# 12-USB_Phy_and_Hub.net
KiCad netlist of a schematic drawn in Altium Designer
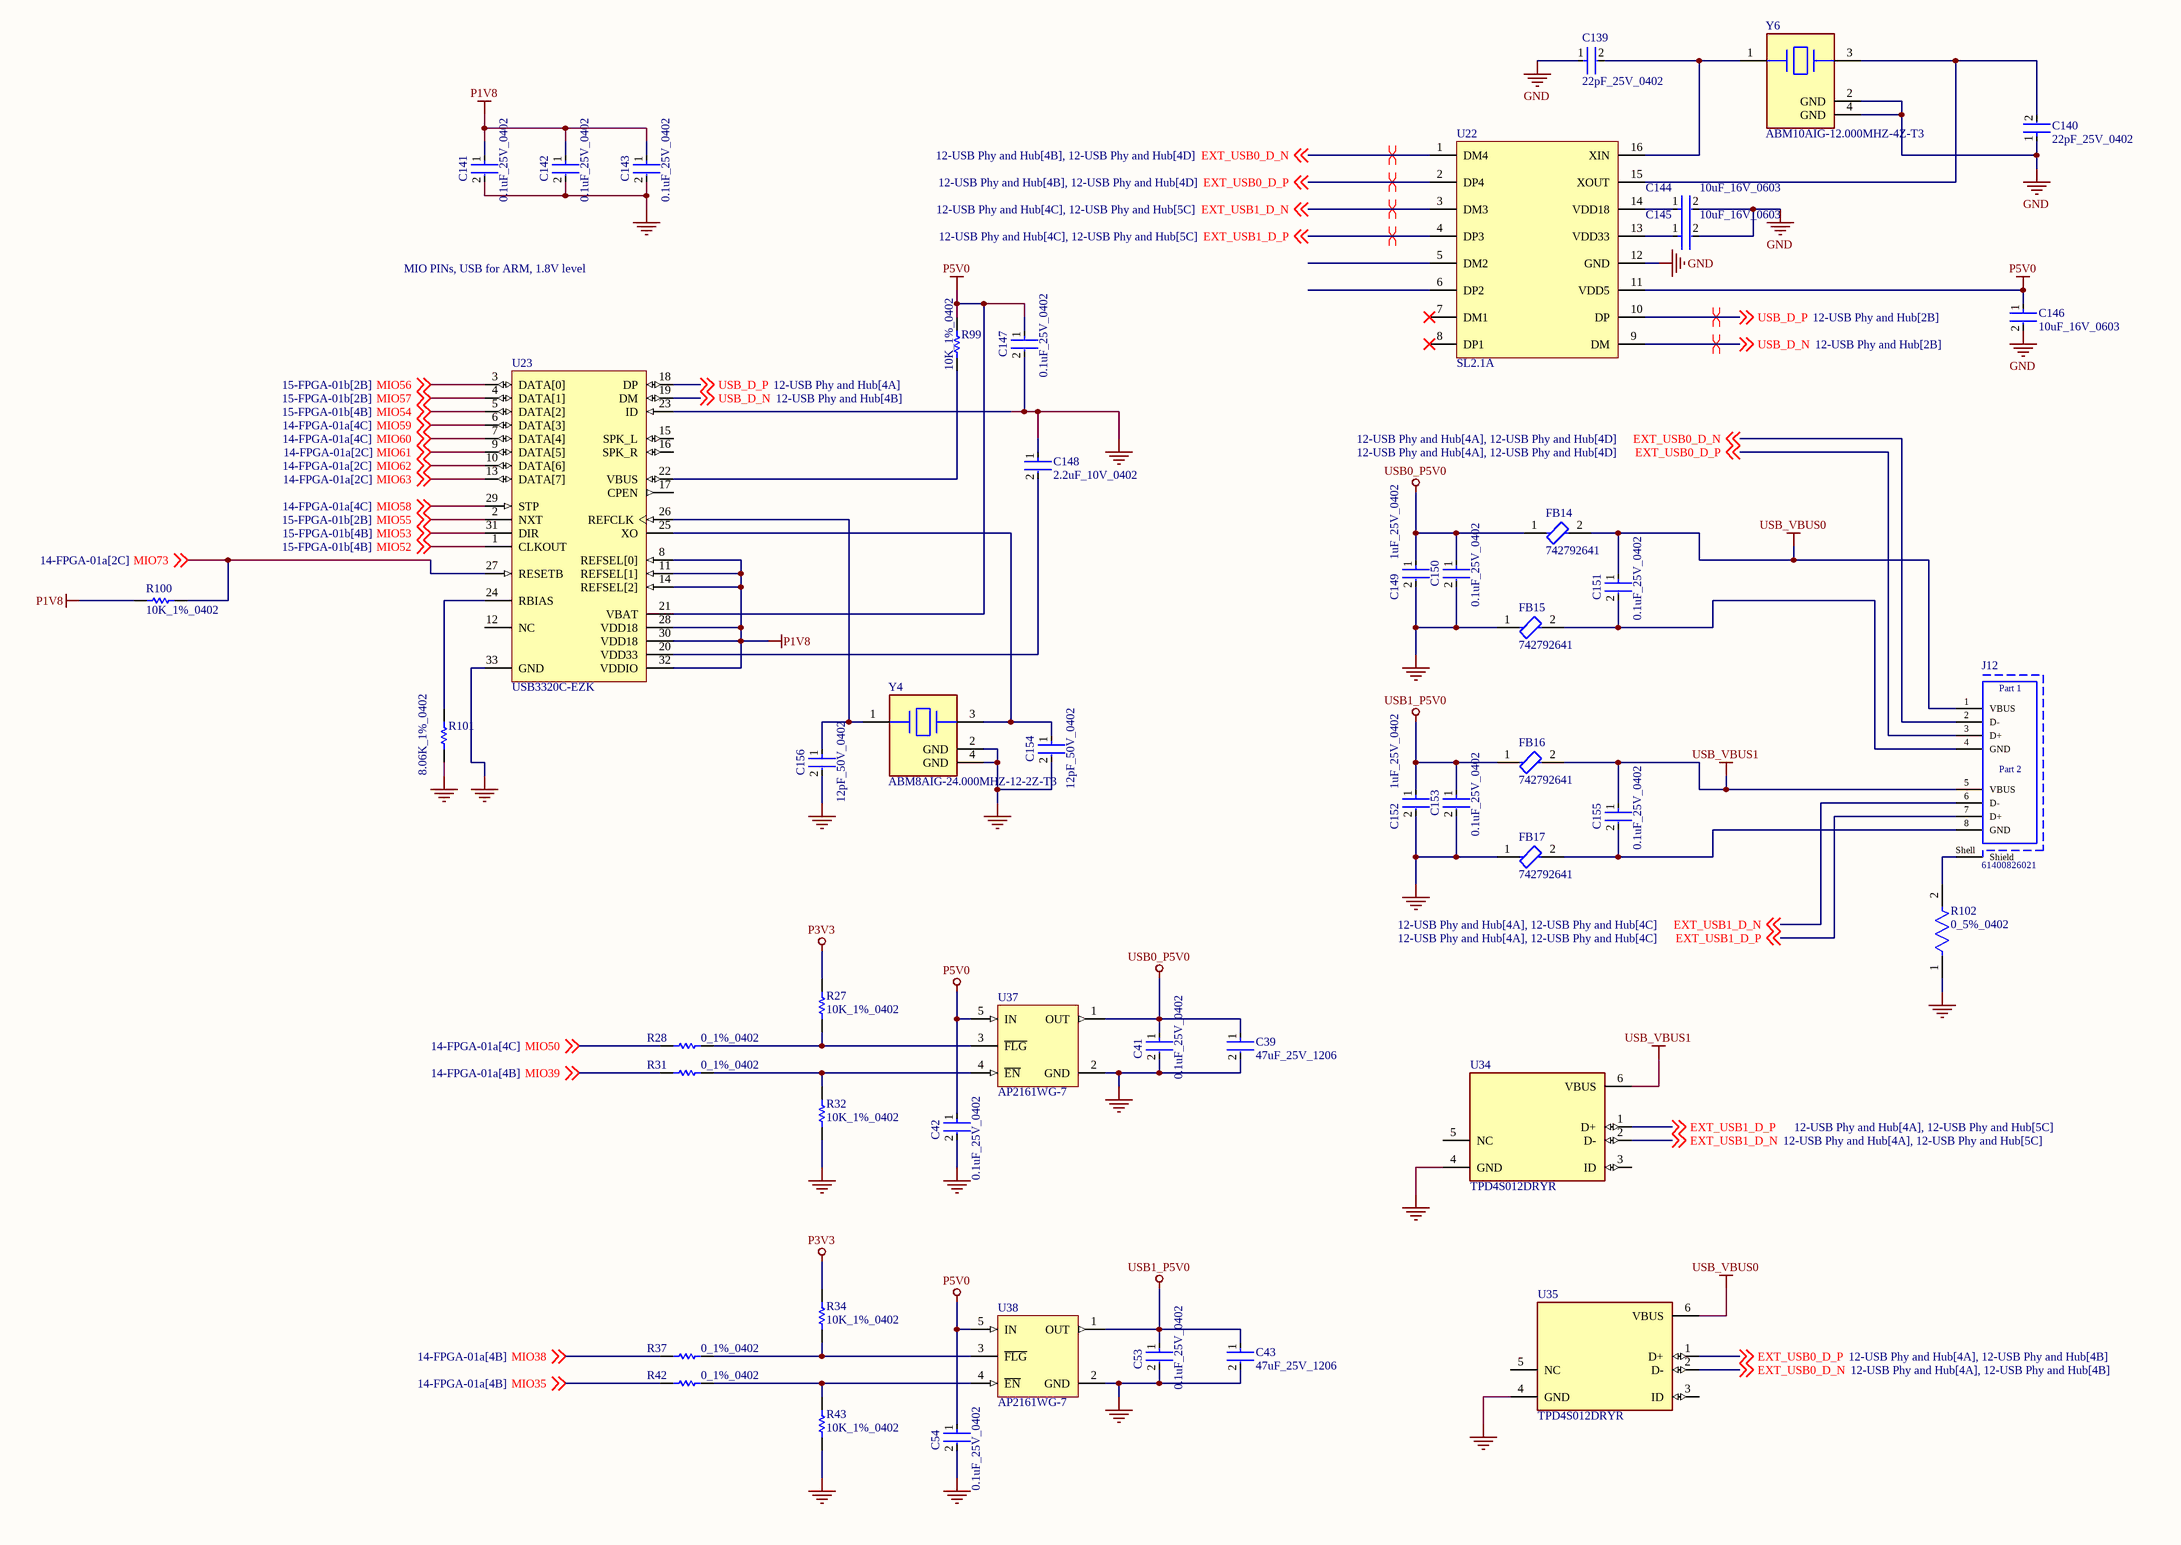
[diagram p0: 12-USB Phy and Hub.SchDoc]

(export (version "E")
  (design (tool "Eeschema 10.0.6"))
  (components
    (comp (ref "C39")
      (value "47uF_25V_1206")
      (footprint "FP-C3216-160-0_2-MFG")
      (description "Multilayer Ceramic Capacitors 47uF ±20% 25V X5R SMD 1206")
      (fields (field (name "VOLTAGE") "25V") (field (name "TOLERANCE") "20%"))
      (libsource (lib "Altium Content Vault") (part "11868f565c42a9108669ba33697ecf6"))
    )
    (comp (ref "C41")
      (value "0.1uF_25V_0402")
      (footprint "FP-0402-L_1_0_1-W_0_5_0_1-IPC_C")
      (description "General Purpose Ceramic Capacitor, 0402, 100nF, 10%, X7R, 15%, 25V")
      (fields (field (name "VOLTAGE") "25V") (field (name "TOLERANCE") "10%"))
      (libsource (lib "Altium Content Vault") (part "b4654b650e69147ec39a6b967a45e02"))
    )
    (comp (ref "C42")
      (value "0.1uF_25V_0402")
      (footprint "FP-0402-L_1_0_1-W_0_5_0_1-IPC_C")
      (description "General Purpose Ceramic Capacitor, 0402, 100nF, 10%, X7R, 15%, 25V")
      (fields (field (name "VOLTAGE") "25V") (field (name "TOLERANCE") "10%"))
      (libsource (lib "Altium Content Vault") (part "b4654b650e69147ec39a6b967a45e02"))
    )
    (comp (ref "C43")
      (value "47uF_25V_1206")
      (footprint "FP-C3216-160-0_2-MFG")
      (description "Multilayer Ceramic Capacitors 47uF ±20% 25V X5R SMD 1206")
      (fields (field (name "VOLTAGE") "25V") (field (name "TOLERANCE") "20%"))
      (libsource (lib "Altium Content Vault") (part "11868f565c42a9108669ba33697ecf6"))
    )
    (comp (ref "C53")
      (value "0.1uF_25V_0402")
      (footprint "FP-0402-L_1_0_1-W_0_5_0_1-IPC_C")
      (description "General Purpose Ceramic Capacitor, 0402, 100nF, 10%, X7R, 15%, 25V")
      (fields (field (name "VOLTAGE") "25V") (field (name "TOLERANCE") "10%"))
      (libsource (lib "Altium Content Vault") (part "b4654b650e69147ec39a6b967a45e02"))
    )
    (comp (ref "C54")
      (value "0.1uF_25V_0402")
      (footprint "FP-0402-L_1_0_1-W_0_5_0_1-IPC_C")
      (description "General Purpose Ceramic Capacitor, 0402, 100nF, 10%, X7R, 15%, 25V")
      (fields (field (name "VOLTAGE") "25V") (field (name "TOLERANCE") "10%"))
      (libsource (lib "Altium Content Vault") (part "b4654b650e69147ec39a6b967a45e02"))
    )
    (comp (ref "C139")
      (value "22pF_25V_0402")
      (footprint "FP-C0402-BB-MFG")
      (description "CAP CER 22PF 25V 5% NP0 0402")
      (fields
        (field (name "MANUFACTURER") "Kemet")
        (field (name "MANUFACTURER PART NUMBER") "C0402C220J3GACTU")
      )
      (libsource (lib "Altium Content Vault") (part "b4654b650e69147ec39a6b967a45e02"))
    )
    (comp (ref "C140")
      (value "22pF_25V_0402")
      (footprint "FP-C0402-BB-MFG")
      (description "CAP CER 22PF 25V 5% NP0 0402")
      (fields
        (field (name "MANUFACTURER") "Kemet")
        (field (name "MANUFACTURER PART NUMBER") "C0402C220J3GACTU")
      )
      (libsource (lib "Altium Content Vault") (part "b4654b650e69147ec39a6b967a45e02"))
    )
    (comp (ref "C141")
      (value "0.1uF_25V_0402")
      (footprint "FP-0402-L_1_0_1-W_0_5_0_1-IPC_C")
      (description "General Purpose Ceramic Capacitor, 0402, 100nF, 10%, X7R, 15%, 25V")
      (fields (field (name "VOLTAGE") "25V") (field (name "TOLERANCE") "10%"))
      (libsource (lib "Altium Content Vault") (part "b4654b650e69147ec39a6b967a45e02"))
    )
    (comp (ref "C142")
      (value "0.1uF_25V_0402")
      (footprint "FP-0402-L_1_0_1-W_0_5_0_1-IPC_C")
      (description "General Purpose Ceramic Capacitor, 0402, 100nF, 10%, X7R, 15%, 25V")
      (fields (field (name "VOLTAGE") "25V") (field (name "TOLERANCE") "10%"))
      (libsource (lib "Altium Content Vault") (part "b4654b650e69147ec39a6b967a45e02"))
    )
    (comp (ref "C143")
      (value "0.1uF_25V_0402")
      (footprint "FP-0402-L_1_0_1-W_0_5_0_1-IPC_C")
      (description "General Purpose Ceramic Capacitor, 0402, 100nF, 10%, X7R, 15%, 25V")
      (fields (field (name "VOLTAGE") "25V") (field (name "TOLERANCE") "10%"))
      (libsource (lib "Altium Content Vault") (part "b4654b650e69147ec39a6b967a45e02"))
    )
    (comp (ref "C144")
      (value "10uF_16V_0603")
      (footprint "FP-0603-L_1_6_0_2-W_0_8_0-MFG")
      (description "Multilayer Ceramic Capacitor 10uF 16V X5R 20% SMD 0603 T/R")
      (fields (field (name "TOLERANCE") "20%"))
      (libsource (lib "Altium Content Vault") (part "b4654b650e69147ec39a6b967a45e02"))
    )
    (comp (ref "C145")
      (value "10uF_16V_0603")
      (footprint "FP-0603-L_1_6_0_2-W_0_8_0-MFG")
      (description "Multilayer Ceramic Capacitor 10uF 16V X5R 20% SMD 0603 T/R")
      (fields (field (name "TOLERANCE") "20%"))
      (libsource (lib "Altium Content Vault") (part "b4654b650e69147ec39a6b967a45e02"))
    )
    (comp (ref "C146")
      (value "10uF_16V_0603")
      (footprint "FP-0603-L_1_6_0_2-W_0_8_0-MFG")
      (description "Multilayer Ceramic Capacitor 10uF 16V X5R 20% SMD 0603 T/R")
      (fields (field (name "TOLERANCE") "20%"))
      (libsource (lib "Altium Content Vault") (part "b4654b650e69147ec39a6b967a45e02"))
    )
    (comp (ref "C147")
      (value "0.1uF_25V_0402")
      (footprint "FP-0402-L_1_0_1-W_0_5_0_1-IPC_C")
      (description "General Purpose Ceramic Capacitor, 0402, 100nF, 10%, X7R, 15%, 25V")
      (fields (field (name "VOLTAGE") "25V") (field (name "TOLERANCE") "10%"))
      (libsource (lib "Altium Content Vault") (part "b4654b650e69147ec39a6b967a45e02"))
    )
    (comp (ref "C148")
      (value "2.2uF_10V_0402")
      (footprint "FP-C1005-050-0_15-0_1-MFG")
      (description "CAP CER 2.2UF 10V X7S 0402")
      (fields (field (name "TOLERANCE") "10%"))
      (libsource (lib "Altium Content Vault") (part "b4654b650e69147ec39a6b967a45e02"))
    )
    (comp (ref "C149")
      (value "1uF_25V_0402")
      (footprint "FP-CL542-IPC_C")
      (description "Cap Ceramic 1uF 25V X5R ±10% SMD 0402 +85°C Paper T/R")
      (fields (field (name "TOLERANCE") "10%"))
      (libsource (lib "Altium Content Vault") (part "b4654b650e69147ec39a6b967a45e02"))
    )
    (comp (ref "C150")
      (value "0.1uF_25V_0402")
      (footprint "FP-0402-L_1_0_1-W_0_5_0_1-IPC_C")
      (description "General Purpose Ceramic Capacitor, 0402, 100nF, 10%, X7R, 15%, 25V")
      (fields (field (name "VOLTAGE") "25V") (field (name "TOLERANCE") "10%"))
      (libsource (lib "Altium Content Vault") (part "b4654b650e69147ec39a6b967a45e02"))
    )
    (comp (ref "C151")
      (value "0.1uF_25V_0402")
      (footprint "FP-0402-L_1_0_1-W_0_5_0_1-IPC_C")
      (description "General Purpose Ceramic Capacitor, 0402, 100nF, 10%, X7R, 15%, 25V")
      (fields (field (name "VOLTAGE") "25V") (field (name "TOLERANCE") "10%"))
      (libsource (lib "Altium Content Vault") (part "b4654b650e69147ec39a6b967a45e02"))
    )
    (comp (ref "C152")
      (value "1uF_25V_0402")
      (footprint "FP-CL542-IPC_C")
      (description "Cap Ceramic 1uF 25V X5R ±10% SMD 0402 +85°C Paper T/R")
      (fields (field (name "TOLERANCE") "10%"))
      (libsource (lib "Altium Content Vault") (part "b4654b650e69147ec39a6b967a45e02"))
    )
    (comp (ref "C153")
      (value "0.1uF_25V_0402")
      (footprint "FP-0402-L_1_0_1-W_0_5_0_1-IPC_C")
      (description "General Purpose Ceramic Capacitor, 0402, 100nF, 10%, X7R, 15%, 25V")
      (fields (field (name "VOLTAGE") "25V") (field (name "TOLERANCE") "10%"))
      (libsource (lib "Altium Content Vault") (part "b4654b650e69147ec39a6b967a45e02"))
    )
    (comp (ref "C154")
      (value "12pF_50V_0402")
      (footprint "FP-0402-L_1_0_1-W_0_5_0_1-IPC_B")
      (description "General Purpose Ceramic Capacitor, 0402, 12pF, 5%, C0G, 30ppm/°C, 50V")
      (fields (field (name "VOLTAGE") "50V") (field (name "TOLERANCE") "5%"))
      (libsource (lib "Altium Content Vault") (part "b4654b650e69147ec39a6b967a45e02"))
    )
    (comp (ref "C155")
      (value "0.1uF_25V_0402")
      (footprint "FP-0402-L_1_0_1-W_0_5_0_1-IPC_C")
      (description "General Purpose Ceramic Capacitor, 0402, 100nF, 10%, X7R, 15%, 25V")
      (fields (field (name "VOLTAGE") "25V") (field (name "TOLERANCE") "10%"))
      (libsource (lib "Altium Content Vault") (part "b4654b650e69147ec39a6b967a45e02"))
    )
    (comp (ref "C156")
      (value "12pF_50V_0402")
      (footprint "FP-0402-L_1_0_1-W_0_5_0_1-IPC_B")
      (description "General Purpose Ceramic Capacitor, 0402, 12pF, 5%, C0G, 30ppm/°C, 50V")
      (fields (field (name "VOLTAGE") "50V") (field (name "TOLERANCE") "5%"))
      (libsource (lib "Altium Content Vault") (part "b4654b650e69147ec39a6b967a45e02"))
    )
    (comp (ref "FB14")
      (value "742792641")
      (footprint "FP-742792641-MFG")
      (description "FERRITE BEAD 300 OHM 0603 1LN")
      (fields (field (name "TOLERANCE") "25%"))
      (libsource (lib "Altium Content Vault") (part "5f30dd21d616792df468990f7003faa"))
    )
    (comp (ref "FB15")
      (value "742792641")
      (footprint "FP-742792641-MFG")
      (description "FERRITE BEAD 300 OHM 0603 1LN")
      (fields (field (name "TOLERANCE") "25%"))
      (libsource (lib "Altium Content Vault") (part "5f30dd21d616792df468990f7003faa"))
    )
    (comp (ref "FB16")
      (value "742792641")
      (footprint "FP-742792641-MFG")
      (description "FERRITE BEAD 300 OHM 0603 1LN")
      (fields (field (name "TOLERANCE") "25%"))
      (libsource (lib "Altium Content Vault") (part "5f30dd21d616792df468990f7003faa"))
    )
    (comp (ref "FB17")
      (value "742792641")
      (footprint "FP-742792641-MFG")
      (description "FERRITE BEAD 300 OHM 0603 1LN")
      (fields (field (name "TOLERANCE") "25%"))
      (libsource (lib "Altium Content Vault") (part "5f30dd21d616792df468990f7003faa"))
    )
    (comp (ref "J12")
      (value "61400826021")
      (footprint "61400826021")
      (description "USB 2.0 Type A Receptacle WR-COM, Stacked Horizontal, THT")
      (fields (field (name "MANUFACTURER") "Wurth Elektronik") (field (name "PUBLISHER") "WurthElektronik"))
      (libsource (lib "Altium Content Vault") (part "WE-USB-8-1SHLD"))
    )
    (comp (ref "R27")
      (value "10K_1%_0402")
      (footprint "RESC1005X40X25NL10T10")
      (fields (field (name "MANUFACTURER") "Bourns") (field (name "PART NUMBER") "CR0402-FX-1002GLF"))
      (libsource (lib "Altium Content Vault") (part "RES"))
    )
    (comp (ref "R28")
      (value "0_1%_0402")
      (footprint "RESC1005X40X25LL05T05")
      (description "Chip Resistor, 0 Ohm, 0.1 W, -55 to 155 degC, 0402 (1005 Metric), RoHS, Tape and Reel")
      (fields (field (name "MANUFACTURER") "Panasonic") (field (name "TOLERANCE") "5%"))
      (libsource (lib "Altium Content Vault") (part "RES-2"))
    )
    (comp (ref "R31")
      (value "0_1%_0402")
      (footprint "RESC1005X40X25LL05T05")
      (description "Chip Resistor, 0 Ohm, 0.1 W, -55 to 155 degC, 0402 (1005 Metric), RoHS, Tape and Reel")
      (fields (field (name "MANUFACTURER") "Panasonic") (field (name "TOLERANCE") "5%"))
      (libsource (lib "Altium Content Vault") (part "RES-2"))
    )
    (comp (ref "R32")
      (value "10K_1%_0402")
      (footprint "RESC1005X40X25NL10T10")
      (fields (field (name "MANUFACTURER") "Bourns") (field (name "PART NUMBER") "CR0402-FX-1002GLF"))
      (libsource (lib "Altium Content Vault") (part "RES"))
    )
    (comp (ref "R34")
      (value "10K_1%_0402")
      (footprint "RESC1005X40X25NL10T10")
      (fields (field (name "MANUFACTURER") "Bourns") (field (name "PART NUMBER") "CR0402-FX-1002GLF"))
      (libsource (lib "Altium Content Vault") (part "RES"))
    )
    (comp (ref "R37")
      (value "0_1%_0402")
      (footprint "RESC1005X40X25LL05T05")
      (description "Chip Resistor, 0 Ohm, 0.1 W, -55 to 155 degC, 0402 (1005 Metric), RoHS, Tape and Reel")
      (fields (field (name "MANUFACTURER") "Panasonic") (field (name "TOLERANCE") "5%"))
      (libsource (lib "Altium Content Vault") (part "RES-2"))
    )
    (comp (ref "R42")
      (value "0_1%_0402")
      (footprint "RESC1005X40X25LL05T05")
      (description "Chip Resistor, 0 Ohm, 0.1 W, -55 to 155 degC, 0402 (1005 Metric), RoHS, Tape and Reel")
      (fields (field (name "MANUFACTURER") "Panasonic") (field (name "TOLERANCE") "5%"))
      (libsource (lib "Altium Content Vault") (part "RES-2"))
    )
    (comp (ref "R43")
      (value "10K_1%_0402")
      (footprint "RESC1005X40X25NL10T10")
      (fields (field (name "MANUFACTURER") "Bourns") (field (name "PART NUMBER") "CR0402-FX-1002GLF"))
      (libsource (lib "Altium Content Vault") (part "RES"))
    )
    (comp (ref "R99")
      (value "10K_1%_0402")
      (footprint "RESC1005X40X25NL10T10")
      (fields (field (name "MANUFACTURER") "Bourns") (field (name "PART NUMBER") "CR0402-FX-1002GLF"))
      (libsource (lib "Altium Content Vault") (part "RES"))
    )
    (comp (ref "R100")
      (value "10K_1%_0402")
      (footprint "RESC1005X40X25NL10T10")
      (fields (field (name "MANUFACTURER") "Bourns") (field (name "PART NUMBER") "CR0402-FX-1002GLF"))
      (libsource (lib "Altium Content Vault") (part "RES"))
    )
    (comp (ref "R101")
      (value "8.06K_1%_0402")
      (footprint "RESC1005X40X25ML05T05")
      (description "Chip Resistor, 8.06 KOhm, +/- 1%, 63 mW, -55 to 155 degC, 0402 (1005 Metric), RoHS, Tape and Reel")
      (fields (field (name "PARTNUMBER") "CRCW04028K06FKED") (field (name "TOLERANCE") "1%"))
      (libsource (lib "Altium Content Vault") (part "RES-2"))
    )
    (comp (ref "R102")
      (value "0_5%_0402")
      (footprint "FP-AC0402-0_37-IPC_B")
      (description "RESISTOR 0402 JUMPER ZERO OHM")
      (fields (field (name "TOLERANCE") "1%"))
      (libsource (lib "Altium Content Vault") (part "1029c3af85768c4190bb7ad29bc67b5"))
    )
    (comp (ref "U22")
      (value "SL2.1A")
      (footprint "IC_SL2.1A")
      (description "USB 2.0 HIGH SPEED 4-PORT HUB CONTROLLER")
      (fields (field (name "MF") "CoreChips ShenZhen CO.,Ltd"))
      (libsource (lib "LotusSound") (part "IC_SL2.1A"))
    )
    (comp (ref "U23")
      (value "USB3320C-EZK")
      (footprint "MCHP-QFN-32-5x5_V2")
      (fields (field (name "MANUFACTURER") "Microchip"))
      (libsource (lib "Altium Content Vault") (part "MCHP-USB3320-32"))
    )
    (comp (ref "U34")
      (value "TPD4S012DRYR")
      (footprint "FP-DRY0006A-MFG")
      (description "TVS DIODE 5.5V 6SON")
      (libsource (lib "Altium Content Vault") (part "0f51f1bc734c3fed0021f16fcfaf2e1"))
    )
    (comp (ref "U35")
      (value "TPD4S012DRYR")
      (footprint "FP-DRY0006A-MFG")
      (description "TVS DIODE 5.5V 6SON")
      (libsource (lib "Altium Content Vault") (part "0f51f1bc734c3fed0021f16fcfaf2e1"))
    )
    (comp (ref "U37")
      (value "AP2161WG-7")
      (footprint "DIOD-SOT25-5_V")
      (fields (field (name "MANUFACTURER") "Diodes-Incorporated"))
      (libsource (lib "Altium Content Vault") (part "DIOD-AP2161-SOT25-5"))
    )
    (comp (ref "U38")
      (value "AP2161WG-7")
      (footprint "DIOD-SOT25-5_V")
      (fields (field (name "MANUFACTURER") "Diodes-Incorporated"))
      (libsource (lib "Altium Content Vault") (part "DIOD-AP2161-SOT25-5"))
    )
    (comp (ref "Y4")
      (value "ABM8AIG-24.000MHZ-12-2Z-T3")
      (footprint "FP-ABM8AIG-MFG")
      (description "Crystal 24MHz ±20ppm (Tol) ±50ppm (Stability) 12pF FUND 50Ω Automotive 4-Pin Ultra Mini-CSMD T/R")
      (libsource (lib "Altium Content Vault") (part "5645ab55de99a04feaa93ac4102b7fe"))
    )
    (comp (ref "Y6")
      (value "ABM10AIG-12.000MHZ-4Z-T3")
      (footprint "FP-ABM10AIG-MFG")
      (description "Crystal 12MHz ±30ppm 10pF SMD-4 2.5mm x 2mm Automotive")
      (libsource (lib "Altium Content Vault") (part "40c3c19da1ce8e2d75e34138d1085e7"))
    )
  )
  (nets
    (net (code "1") (name "EXT_USB0_D_N") (class "Default")
      (node (ref "J12") (pin "2") (pinfunction "D-_2") (pintype "passive"))
      (node (ref "U22") (pin "1") (pinfunction "DM4_1") (pintype "passive"))
      (node (ref "U35") (pin "2") (pinfunction "D-_2") (pintype "bidirectional"))
    )
    (net (code "2") (name "EXT_USB0_D_P") (class "Default")
      (node (ref "J12") (pin "3") (pinfunction "D+_3") (pintype "passive"))
      (node (ref "U22") (pin "2") (pinfunction "DP4_2") (pintype "passive"))
      (node (ref "U35") (pin "1") (pinfunction "D+_1") (pintype "bidirectional"))
    )
    (net (code "3") (name "EXT_USB1_D_N") (class "Default")
      (node (ref "J12") (pin "6") (pinfunction "D-_6") (pintype "passive"))
      (node (ref "U22") (pin "3") (pinfunction "DM3_3") (pintype "passive"))
      (node (ref "U34") (pin "2") (pinfunction "D-_2") (pintype "bidirectional"))
    )
    (net (code "4") (name "EXT_USB1_D_P") (class "Default")
      (node (ref "J12") (pin "7") (pinfunction "D+_7") (pintype "passive"))
      (node (ref "U22") (pin "4") (pinfunction "DP3_4") (pintype "passive"))
      (node (ref "U34") (pin "1") (pinfunction "D+_1") (pintype "bidirectional"))
    )
    (net (code "5") (name "GND") (class "Default")
      (node (ref "C139") (pin "1") (pinfunction "1_1") (pintype "passive"))
      (node (ref "C140") (pin "1") (pinfunction "1_1") (pintype "passive"))
      (node (ref "C141") (pin "2") (pinfunction "2_2") (pintype "passive"))
      (node (ref "C142") (pin "2") (pinfunction "2_2") (pintype "passive"))
      (node (ref "C143") (pin "2") (pinfunction "2_2") (pintype "passive"))
      (node (ref "C144") (pin "2") (pinfunction "2_2") (pintype "passive"))
      (node (ref "C145") (pin "2") (pinfunction "2_2") (pintype "passive"))
      (node (ref "C146") (pin "2") (pinfunction "2_2") (pintype "passive"))
      (node (ref "C147") (pin "2") (pinfunction "2_2") (pintype "passive"))
      (node (ref "C148") (pin "1") (pinfunction "1_1") (pintype "passive"))
      (node (ref "C149") (pin "2") (pinfunction "2_2") (pintype "passive"))
      (node (ref "C150") (pin "2") (pinfunction "2_2") (pintype "passive"))
      (node (ref "C152") (pin "2") (pinfunction "2_2") (pintype "passive"))
      (node (ref "C153") (pin "2") (pinfunction "2_2") (pintype "passive"))
      (node (ref "C154") (pin "2") (pinfunction "2_2") (pintype "passive"))
      (node (ref "C156") (pin "2") (pinfunction "2_2") (pintype "passive"))
      (node (ref "C39") (pin "2") (pinfunction "2_2") (pintype "passive"))
      (node (ref "C41") (pin "2") (pinfunction "2_2") (pintype "passive"))
      (node (ref "C42") (pin "2") (pinfunction "2_2") (pintype "passive"))
      (node (ref "C43") (pin "2") (pinfunction "2_2") (pintype "passive"))
      (node (ref "C53") (pin "2") (pinfunction "2_2") (pintype "passive"))
      (node (ref "C54") (pin "2") (pinfunction "2_2") (pintype "passive"))
      (node (ref "FB15") (pin "1") (pinfunction "1_1") (pintype "passive"))
      (node (ref "FB17") (pin "1") (pinfunction "1_1") (pintype "passive"))
      (node (ref "R101") (pin "1") (pinfunction "1_1") (pintype "passive"))
      (node (ref "R102") (pin "1") (pinfunction "1_1") (pintype "passive"))
      (node (ref "R32") (pin "1") (pinfunction "1_1") (pintype "passive"))
      (node (ref "R43") (pin "1") (pinfunction "1_1") (pintype "passive"))
      (node (ref "U22") (pin "12") (pinfunction "GND_12") (pintype "passive"))
      (node (ref "U23") (pin "23") (pinfunction "ID_23") (pintype "input"))
      (node (ref "U23") (pin "33") (pinfunction "GND_33") (pintype "power_in"))
      (node (ref "U34") (pin "4") (pinfunction "GND_4") (pintype "power_in"))
      (node (ref "U35") (pin "4") (pinfunction "GND_4") (pintype "power_in"))
      (node (ref "U37") (pin "2") (pinfunction "GND_2") (pintype "power_in"))
      (node (ref "U38") (pin "2") (pinfunction "GND_2") (pintype "power_in"))
      (node (ref "Y4") (pin "2") (pinfunction "GND_2") (pintype "power_in"))
      (node (ref "Y4") (pin "4") (pinfunction "GND_4") (pintype "power_in"))
      (node (ref "Y6") (pin "2") (pinfunction "GND_2") (pintype "power_in"))
      (node (ref "Y6") (pin "4") (pinfunction "GND_4") (pintype "power_in"))
    )
    (net (code "6") (name "MIO35") (class "Default")
      (node (ref "R42") (pin "1") (pinfunction "1_1") (pintype "passive"))
    )
    (net (code "7") (name "MIO38") (class "Default")
      (node (ref "R37") (pin "1") (pinfunction "1_1") (pintype "passive"))
    )
    (net (code "8") (name "MIO39") (class "Default")
      (node (ref "R31") (pin "1") (pinfunction "1_1") (pintype "passive"))
    )
    (net (code "9") (name "MIO50") (class "Default")
      (node (ref "R28") (pin "1") (pinfunction "1_1") (pintype "passive"))
    )
    (net (code "10") (name "MIO52") (class "Default")
      (node (ref "U23") (pin "1") (pinfunction "CLKOUT_1") (pintype "tri_state"))
    )
    (net (code "11") (name "MIO53") (class "Default")
      (node (ref "U23") (pin "31") (pinfunction "DIR_31") (pintype "tri_state"))
    )
    (net (code "12") (name "MIO54") (class "Default")
      (node (ref "U23") (pin "5") (pinfunction "DATA[2]_5") (pintype "bidirectional"))
    )
    (net (code "13") (name "MIO55") (class "Default")
      (node (ref "U23") (pin "2") (pinfunction "NXT_2") (pintype "tri_state"))
    )
    (net (code "14") (name "MIO56") (class "Default")
      (node (ref "U23") (pin "3") (pinfunction "DATA[0]_3") (pintype "bidirectional"))
    )
    (net (code "15") (name "MIO57") (class "Default")
      (node (ref "U23") (pin "4") (pinfunction "DATA[1]_4") (pintype "bidirectional"))
    )
    (net (code "16") (name "MIO58") (class "Default")
      (node (ref "U23") (pin "29") (pinfunction "STP_29") (pintype "input"))
    )
    (net (code "17") (name "MIO59") (class "Default")
      (node (ref "U23") (pin "6") (pinfunction "DATA[3]_6") (pintype "bidirectional"))
    )
    (net (code "18") (name "MIO60") (class "Default")
      (node (ref "U23") (pin "7") (pinfunction "DATA[4]_7") (pintype "bidirectional"))
    )
    (net (code "19") (name "MIO61") (class "Default")
      (node (ref "U23") (pin "9") (pinfunction "DATA[5]_9") (pintype "bidirectional"))
    )
    (net (code "20") (name "MIO62") (class "Default")
      (node (ref "U23") (pin "10") (pinfunction "DATA[6]_10") (pintype "bidirectional"))
    )
    (net (code "21") (name "MIO63") (class "Default")
      (node (ref "U23") (pin "13") (pinfunction "DATA[7]_13") (pintype "bidirectional"))
    )
    (net (code "22") (name "MIO73") (class "Default")
      (node (ref "R100") (pin "2") (pinfunction "2_2") (pintype "passive"))
      (node (ref "U23") (pin "27") (pinfunction "RESETB_27") (pintype "input"))
    )
    (net (code "23") (name "Net-(C151-Pad2)") (class "Default")
      (node (ref "C151") (pin "2") (pinfunction "2_2") (pintype "passive"))
      (node (ref "FB15") (pin "2") (pinfunction "2_2") (pintype "passive"))
      (node (ref "J12") (pin "4") (pinfunction "GND_4") (pintype "passive"))
    )
    (net (code "24") (name "Net-(C155-Pad2)") (class "Default")
      (node (ref "C155") (pin "2") (pinfunction "2_2") (pintype "passive"))
      (node (ref "FB17") (pin "2") (pinfunction "2_2") (pintype "passive"))
      (node (ref "J12") (pin "8") (pinfunction "GND_8") (pintype "passive"))
    )
    (net (code "25") (name "Net-(J12-Shield)") (class "Default")
      (node (ref "J12") (pin "Shell") (pinfunction "Shield_Shell") (pintype "passive"))
      (node (ref "R102") (pin "2") (pinfunction "2_2") (pintype "passive"))
    )
    (net (code "26") (name "Net-(U22-VDD18)") (class "Default")
      (node (ref "C144") (pin "1") (pinfunction "1_1") (pintype "passive"))
      (node (ref "U22") (pin "14") (pinfunction "VDD18_14") (pintype "passive"))
    )
    (net (code "27") (name "Net-(U22-VDD33)") (class "Default")
      (node (ref "C145") (pin "1") (pinfunction "1_1") (pintype "passive"))
      (node (ref "U22") (pin "13") (pinfunction "VDD33_13") (pintype "passive"))
    )
    (net (code "28") (name "Net-(U22-XIN)") (class "Default")
      (node (ref "C139") (pin "2") (pinfunction "2_2") (pintype "passive"))
      (node (ref "U22") (pin "16") (pinfunction "XIN_16") (pintype "passive"))
      (node (ref "Y6") (pin "1") (pinfunction "1_Crystal_1") (pintype "passive"))
    )
    (net (code "29") (name "Net-(U22-XOUT)") (class "Default")
      (node (ref "C140") (pin "2") (pinfunction "2_2") (pintype "passive"))
      (node (ref "U22") (pin "15") (pinfunction "XOUT_15") (pintype "passive"))
      (node (ref "Y6") (pin "3") (pinfunction "2_Crystal_3") (pintype "passive"))
    )
    (net (code "30") (name "Net-(U23-RBIAS)") (class "Default")
      (node (ref "R101") (pin "2") (pinfunction "2_2") (pintype "passive"))
      (node (ref "U23") (pin "24") (pinfunction "RBIAS_24") (pintype "passive"))
    )
    (net (code "31") (name "Net-(U23-REFCLK)") (class "Default")
      (node (ref "C156") (pin "1") (pinfunction "1_1") (pintype "passive"))
      (node (ref "U23") (pin "26") (pinfunction "REFCLK_26") (pintype "input"))
      (node (ref "Y4") (pin "1") (pinfunction "1_1") (pintype "passive"))
    )
    (net (code "32") (name "Net-(U23-VBUS)") (class "Default")
      (node (ref "R99") (pin "1") (pinfunction "1_1") (pintype "passive"))
      (node (ref "U23") (pin "22") (pinfunction "VBUS_22") (pintype "bidirectional"))
    )
    (net (code "33") (name "Net-(U23-VDD33)") (class "Default")
      (node (ref "C148") (pin "2") (pinfunction "2_2") (pintype "passive"))
      (node (ref "U23") (pin "20") (pinfunction "VDD33_20") (pintype "power_in"))
    )
    (net (code "34") (name "Net-(U23-XO)") (class "Default")
      (node (ref "C154") (pin "1") (pinfunction "1_1") (pintype "passive"))
      (node (ref "U23") (pin "25") (pinfunction "XO_25") (pintype "passive"))
      (node (ref "Y4") (pin "3") (pinfunction "3_3") (pintype "passive"))
    )
    (net (code "35") (name "Net-(U37-~{EN})") (class "Default")
      (node (ref "R31") (pin "2") (pinfunction "2_2") (pintype "passive"))
      (node (ref "R32") (pin "2") (pinfunction "2_2") (pintype "passive"))
      (node (ref "U37") (pin "4") (pinfunction "~{EN}_4") (pintype "input"))
    )
    (net (code "36") (name "Net-(U37-~{FLG})") (class "Default")
      (node (ref "R27") (pin "1") (pinfunction "1_1") (pintype "passive"))
      (node (ref "R28") (pin "2") (pinfunction "2_2") (pintype "passive"))
      (node (ref "U37") (pin "3") (pinfunction "~{FLG}_3") (pintype "open_collector"))
    )
    (net (code "37") (name "Net-(U38-~{EN})") (class "Default")
      (node (ref "R42") (pin "2") (pinfunction "2_2") (pintype "passive"))
      (node (ref "R43") (pin "2") (pinfunction "2_2") (pintype "passive"))
      (node (ref "U38") (pin "4") (pinfunction "~{EN}_4") (pintype "input"))
    )
    (net (code "38") (name "Net-(U38-~{FLG})") (class "Default")
      (node (ref "R34") (pin "1") (pinfunction "1_1") (pintype "passive"))
      (node (ref "R37") (pin "2") (pinfunction "2_2") (pintype "passive"))
      (node (ref "U38") (pin "3") (pinfunction "~{FLG}_3") (pintype "open_collector"))
    )
    (net (code "39") (name "P1V8") (class "Default")
      (node (ref "C141") (pin "1") (pinfunction "1_1") (pintype "passive"))
      (node (ref "C142") (pin "1") (pinfunction "1_1") (pintype "passive"))
      (node (ref "C143") (pin "1") (pinfunction "1_1") (pintype "passive"))
      (node (ref "R100") (pin "1") (pinfunction "1_1") (pintype "passive"))
      (node (ref "U23") (pin "11") (pinfunction "REFSEL[1]_11") (pintype "input"))
      (node (ref "U23") (pin "14") (pinfunction "REFSEL[2]_14") (pintype "input"))
      (node (ref "U23") (pin "28") (pinfunction "VDD18_28") (pintype "power_in"))
      (node (ref "U23") (pin "30") (pinfunction "VDD18_30") (pintype "power_in"))
      (node (ref "U23") (pin "32") (pinfunction "VDDIO_32") (pintype "power_in"))
      (node (ref "U23") (pin "8") (pinfunction "REFSEL[0]_8") (pintype "input"))
    )
    (net (code "40") (name "P3V3") (class "Default")
      (node (ref "R27") (pin "2") (pinfunction "2_2") (pintype "passive"))
      (node (ref "R34") (pin "2") (pinfunction "2_2") (pintype "passive"))
    )
    (net (code "41") (name "P5V0") (class "Default")
      (node (ref "C146") (pin "1") (pinfunction "1_1") (pintype "passive"))
      (node (ref "C147") (pin "1") (pinfunction "1_1") (pintype "passive"))
      (node (ref "C42") (pin "1") (pinfunction "1_1") (pintype "passive"))
      (node (ref "C54") (pin "1") (pinfunction "1_1") (pintype "passive"))
      (node (ref "R99") (pin "2") (pinfunction "2_2") (pintype "passive"))
      (node (ref "U22") (pin "11") (pinfunction "VDD5_11") (pintype "passive"))
      (node (ref "U23") (pin "21") (pinfunction "VBAT_21") (pintype "power_in"))
      (node (ref "U37") (pin "5") (pinfunction "IN_5") (pintype "input"))
      (node (ref "U38") (pin "5") (pinfunction "IN_5") (pintype "input"))
    )
    (net (code "42") (name "USB0_P5V0") (class "Default")
      (node (ref "C149") (pin "1") (pinfunction "1_1") (pintype "passive"))
      (node (ref "C150") (pin "1") (pinfunction "1_1") (pintype "passive"))
      (node (ref "C39") (pin "1") (pinfunction "1_1") (pintype "passive"))
      (node (ref "C41") (pin "1") (pinfunction "1_1") (pintype "passive"))
      (node (ref "FB14") (pin "1") (pinfunction "1_1") (pintype "passive"))
      (node (ref "U37") (pin "1") (pinfunction "OUT_1") (pintype "output"))
    )
    (net (code "43") (name "USB1_P5V0") (class "Default")
      (node (ref "C152") (pin "1") (pinfunction "1_1") (pintype "passive"))
      (node (ref "C153") (pin "1") (pinfunction "1_1") (pintype "passive"))
      (node (ref "C43") (pin "1") (pinfunction "1_1") (pintype "passive"))
      (node (ref "C53") (pin "1") (pinfunction "1_1") (pintype "passive"))
      (node (ref "FB16") (pin "1") (pinfunction "1_1") (pintype "passive"))
      (node (ref "U38") (pin "1") (pinfunction "OUT_1") (pintype "output"))
    )
    (net (code "44") (name "USB_D_N") (class "Default")
      (node (ref "U22") (pin "9") (pinfunction "DM_9") (pintype "passive"))
      (node (ref "U23") (pin "19") (pinfunction "DM_19") (pintype "bidirectional"))
    )
    (net (code "45") (name "USB_D_P") (class "Default")
      (node (ref "U22") (pin "10") (pinfunction "DP_10") (pintype "passive"))
      (node (ref "U23") (pin "18") (pinfunction "DP_18") (pintype "bidirectional"))
    )
    (net (code "46") (name "USB_VBUS0") (class "Default")
      (node (ref "C151") (pin "1") (pinfunction "1_1") (pintype "passive"))
      (node (ref "FB14") (pin "2") (pinfunction "2_2") (pintype "passive"))
      (node (ref "J12") (pin "1") (pinfunction "VBUS_1") (pintype "passive"))
      (node (ref "U35") (pin "6") (pinfunction "VBUS_6") (pintype "passive"))
    )
    (net (code "47") (name "USB_VBUS1") (class "Default")
      (node (ref "C155") (pin "1") (pinfunction "1_1") (pintype "passive"))
      (node (ref "FB16") (pin "2") (pinfunction "2_2") (pintype "passive"))
      (node (ref "J12") (pin "5") (pinfunction "VBUS_5") (pintype "passive"))
      (node (ref "U34") (pin "6") (pinfunction "VBUS_6") (pintype "passive"))
    )
    (net (code "48") (name "unconnected-(U22-DM1-Pad7)") (class "Default")
      (node (ref "U22") (pin "7") (pinfunction "DM1_7") (pintype "passive+no_connect"))
    )
    (net (code "49") (name "unconnected-(U22-DM2-Pad5)") (class "Default")
      (node (ref "U22") (pin "5") (pinfunction "DM2_5") (pintype "passive"))
    )
    (net (code "50") (name "unconnected-(U22-DP1-Pad8)") (class "Default")
      (node (ref "U22") (pin "8") (pinfunction "DP1_8") (pintype "passive+no_connect"))
    )
    (net (code "51") (name "unconnected-(U22-DP2-Pad6)") (class "Default")
      (node (ref "U22") (pin "6") (pinfunction "DP2_6") (pintype "passive"))
    )
    (net (code "52") (name "unconnected-(U23-CPEN-Pad17)") (class "Default")
      (node (ref "U23") (pin "17") (pinfunction "CPEN_17") (pintype "output"))
    )
    (net (code "53") (name "unconnected-(U23-NC-Pad12)") (class "Default")
      (node (ref "U23") (pin "12") (pinfunction "NC_12") (pintype "passive"))
    )
    (net (code "54") (name "unconnected-(U23-SPK_L-Pad15)") (class "Default")
      (node (ref "U23") (pin "15") (pinfunction "SPK_L_15") (pintype "bidirectional"))
    )
    (net (code "55") (name "unconnected-(U23-SPK_R-Pad16)") (class "Default")
      (node (ref "U23") (pin "16") (pinfunction "SPK_R_16") (pintype "bidirectional"))
    )
    (net (code "56") (name "unconnected-(U34-ID-Pad3)") (class "Default")
      (node (ref "U34") (pin "3") (pinfunction "ID_3") (pintype "bidirectional"))
    )
    (net (code "57") (name "unconnected-(U34-NC-Pad5)") (class "Default")
      (node (ref "U34") (pin "5") (pinfunction "NC_5") (pintype "passive"))
    )
    (net (code "58") (name "unconnected-(U35-ID-Pad3)") (class "Default")
      (node (ref "U35") (pin "3") (pinfunction "ID_3") (pintype "bidirectional"))
    )
    (net (code "59") (name "unconnected-(U35-NC-Pad5)") (class "Default")
      (node (ref "U35") (pin "5") (pinfunction "NC_5") (pintype "passive"))
    )
  )
)
